# Sheet1.net
KiCad netlist of a schematic drawn in Altium Designer
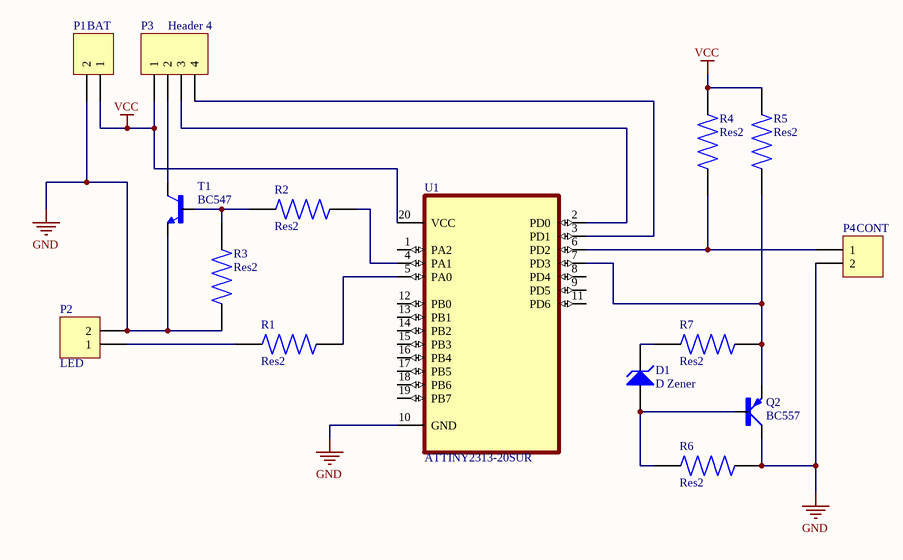
[diagram p0: Sheet1.SchDoc]

(export (version "E")
  (design (tool "Eeschema 10.0.6"))
  (components
    (comp (ref "D1")
      (value "D Zener")
      (footprint "DIODE-0.7")
      (description "Zener Diode")
      (fields (field (name "PUBLISHER") "Altium Limited"))
      (libsource (lib "Miscellaneous Devices") (part "D Zener"))
    )
    (comp (ref "P1")
      (value "BAT")
      (footprint "HDR1X2")
      (description "Header, 2-Pin")
      (fields (field (name "PUBLISHER") "Altium Limited"))
      (libsource (lib "Miscellaneous Connectors") (part "Header 2"))
    )
    (comp (ref "P2")
      (value "LED")
      (footprint "HDR1X2")
      (description "Header, 2-Pin")
      (fields (field (name "PUBLISHER") "Altium Limited"))
      (libsource (lib "") (part "Header 2_1"))
    )
    (comp (ref "P3")
      (value "Header 4")
      (footprint "HDR1X4")
      (description "Header, 4-Pin")
      (fields (field (name "PUBLISHER") "Altium Limited"))
      (libsource (lib "Miscellaneous Connectors") (part "Header 4"))
    )
    (comp (ref "P4")
      (value "CONT")
      (footprint "HDR1X2")
      (description "Header, 2-Pin")
      (fields (field (name "PUBLISHER") "Altium Limited"))
      (libsource (lib "Miscellaneous Connectors") (part "Header 2"))
    )
    (comp (ref "Q2")
      (value "BC557")
      (footprint "SOT54A")
      (description "Bipolar (BJT) Transistor PNP 45 V 100 mA 320MHz 625 mW Through Hole TO-92 (TO-226)")
      (fields (field (name "MF") "ON Semiconductor"))
      (libsource (lib "BC557") (part "BC557"))
    )
    (comp (ref "R1")
      (value "Res2")
      (footprint "AXIAL-0.4")
      (description "Fixed Resistor CRGCQ 1206 10K 5%")
      (fields (field (name "MF") "TE Connectivity") (field (name "MP") "CRGCQ1206J10K"))
      (libsource (lib "CRGCQ1206J10K") (part "CRGCQ1206J10K"))
    )
    (comp (ref "R2")
      (value "Res2")
      (footprint "AXIAL-0.4")
      (description "Fixed Resistor CRGCQ 1206 10K 5%")
      (fields (field (name "MF") "TE Connectivity") (field (name "MP") "CRGCQ1206J10K"))
      (libsource (lib "CRGCQ1206J10K") (part "CRGCQ1206J10K"))
    )
    (comp (ref "R3")
      (value "Res2")
      (footprint "AXIAL-0.4")
      (description "Fixed Resistor CRGCQ 1206 10K 5%")
      (fields (field (name "MF") "TE Connectivity") (field (name "MP") "CRGCQ1206J10K"))
      (libsource (lib "CRGCQ1206J10K") (part "CRGCQ1206J10K"))
    )
    (comp (ref "R4")
      (value "Res2")
      (footprint "AXIAL-0.4")
      (description "Fixed Resistor CRGCQ 1206 10K 5%")
      (fields (field (name "MF") "TE Connectivity") (field (name "MP") "CRGCQ1206J10K"))
      (libsource (lib "CRGCQ1206J10K") (part "CRGCQ1206J10K"))
    )
    (comp (ref "R5")
      (value "Res2")
      (footprint "AXIAL-0.4")
      (description "Fixed Resistor CRGCQ 1206 10K 5%")
      (fields (field (name "MF") "TE Connectivity") (field (name "MP") "CRGCQ1206J10K"))
      (libsource (lib "CRGCQ1206J10K") (part "CRGCQ1206J10K"))
    )
    (comp (ref "R6")
      (value "Res2")
      (footprint "AXIAL-0.4")
      (description "Fixed Resistor CRGCQ 1206 10K 5%")
      (fields (field (name "MF") "TE Connectivity") (field (name "MP") "CRGCQ1206J10K"))
      (libsource (lib "") (part "CRGCQ1206J10K_2"))
    )
    (comp (ref "R7")
      (value "Res2")
      (footprint "AXIAL-0.4")
      (description "Fixed Resistor CRGCQ 1206 10K 5%")
      (fields (field (name "MF") "TE Connectivity") (field (name "MP") "CRGCQ1206J10K"))
      (libsource (lib "") (part "CRGCQ1206J10K_1"))
    )
    (comp (ref "T1")
      (value "BC547")
      (footprint "TO92")
      (description "Trans GP BJT NPN 45V 0.1A 500mW 3-Pin TO-92 T/R")
      (fields (field (name "MF") "ON Semiconductor"))
      (libsource (lib "BC547") (part "BC547"))
    )
    (comp (ref "U1")
      (value "ATTINY2313-20SUR")
      (footprint "SOIC127P1032X265-20N")
      (description "AVR series Microcontroller IC 8-Bit 20MHz 2KB (1K x 16) FLASH 20-SOIC")
      (fields (field (name "MF") "Microchip Technology"))
      (libsource (lib "ATTINY2313-20SUR") (part "ATTINY2313-20SUR"))
    )
  )
  (nets
    (net (code "1") (name "GND") (class "Default")
      (node (ref "P1") (pin "2") (pinfunction "2_2") (pintype "passive"))
      (node (ref "P2") (pin "2") (pinfunction "2_2") (pintype "passive"))
      (node (ref "P4") (pin "2") (pinfunction "2_2") (pintype "passive"))
      (node (ref "Q2") (pin "C") (pinfunction "C_C") (pintype "passive"))
      (node (ref "R3") (pin "1") (pinfunction "1_1") (pintype "passive"))
      (node (ref "R6") (pin "1") (pinfunction "1_1") (pintype "passive"))
      (node (ref "T1") (pin "1") (pinfunction "E_1") (pintype "passive"))
      (node (ref "U1") (pin "10") (pinfunction "GND_10") (pintype "passive"))
    )
    (net (code "2") (name "Net-(D1-A)") (class "Default")
      (node (ref "D1") (pin "1") (pinfunction "A_1") (pintype "passive"))
      (node (ref "Q2") (pin "B") (pinfunction "B_B") (pintype "passive"))
      (node (ref "R6") (pin "2") (pinfunction "2_2") (pintype "passive"))
    )
    (net (code "3") (name "Net-(D1-K)") (class "Default")
      (node (ref "D1") (pin "2") (pinfunction "K_2") (pintype "passive"))
      (node (ref "R7") (pin "1") (pinfunction "1_1") (pintype "passive"))
    )
    (net (code "4") (name "Net-(P2-Pad1)") (class "Default")
      (node (ref "P2") (pin "1") (pinfunction "1_1") (pintype "passive"))
      (node (ref "R1") (pin "1") (pinfunction "1_1") (pintype "passive"))
    )
    (net (code "5") (name "Net-(T1-B)") (class "Default")
      (node (ref "R2") (pin "1") (pinfunction "1_1") (pintype "passive"))
      (node (ref "R3") (pin "2") (pinfunction "2_2") (pintype "passive"))
      (node (ref "T1") (pin "2") (pinfunction "B_2") (pintype "passive"))
    )
    (net (code "6") (name "Net-(T1-C)") (class "Default")
      (node (ref "P3") (pin "2") (pinfunction "2_2") (pintype "passive"))
      (node (ref "T1") (pin "3") (pinfunction "C_3") (pintype "passive"))
    )
    (net (code "7") (name "Net-(U1-PA0)") (class "Default")
      (node (ref "R1") (pin "2") (pinfunction "2_2") (pintype "passive"))
      (node (ref "U1") (pin "5") (pinfunction "PA0_5") (pintype "bidirectional"))
    )
    (net (code "8") (name "Net-(U1-PA1)") (class "Default")
      (node (ref "R2") (pin "2") (pinfunction "2_2") (pintype "passive"))
      (node (ref "U1") (pin "4") (pinfunction "PA1_4") (pintype "bidirectional"))
    )
    (net (code "9") (name "Net-(U1-PD0)") (class "Default")
      (node (ref "P3") (pin "3") (pinfunction "3_3") (pintype "passive"))
      (node (ref "U1") (pin "2") (pinfunction "PD0_2") (pintype "bidirectional"))
    )
    (net (code "10") (name "Net-(U1-PD1)") (class "Default")
      (node (ref "P3") (pin "4") (pinfunction "4_4") (pintype "passive"))
      (node (ref "U1") (pin "3") (pinfunction "PD1_3") (pintype "bidirectional"))
    )
    (net (code "11") (name "Net-(U1-PD2)") (class "Default")
      (node (ref "P4") (pin "1") (pinfunction "1_1") (pintype "passive"))
      (node (ref "R4") (pin "1") (pinfunction "1_1") (pintype "passive"))
      (node (ref "U1") (pin "6") (pinfunction "PD2_6") (pintype "bidirectional"))
    )
    (net (code "12") (name "Net-(U1-PD3)") (class "Default")
      (node (ref "Q2") (pin "E") (pinfunction "E_E") (pintype "passive"))
      (node (ref "R5") (pin "1") (pinfunction "1_1") (pintype "passive"))
      (node (ref "R7") (pin "1") (pinfunction "1_1") (pintype "passive"))
      (node (ref "U1") (pin "7") (pinfunction "PD3_7") (pintype "bidirectional"))
    )
    (net (code "13") (name "VCC") (class "Default")
      (node (ref "P1") (pin "1") (pinfunction "1_1") (pintype "passive"))
      (node (ref "P3") (pin "1") (pinfunction "1_1") (pintype "passive"))
      (node (ref "R4") (pin "2") (pinfunction "2_2") (pintype "passive"))
      (node (ref "R5") (pin "2") (pinfunction "2_2") (pintype "passive"))
      (node (ref "U1") (pin "20") (pinfunction "VCC_20") (pintype "power_in"))
    )
    (net (code "14") (name "unconnected-(U1-PA2-Pad1)") (class "Default")
      (node (ref "U1") (pin "1") (pinfunction "PA2_1") (pintype "bidirectional"))
    )
    (net (code "15") (name "unconnected-(U1-PB0-Pad12)") (class "Default")
      (node (ref "U1") (pin "12") (pinfunction "PB0_12") (pintype "bidirectional"))
    )
    (net (code "16") (name "unconnected-(U1-PB1-Pad13)") (class "Default")
      (node (ref "U1") (pin "13") (pinfunction "PB1_13") (pintype "bidirectional"))
    )
    (net (code "17") (name "unconnected-(U1-PB2-Pad14)") (class "Default")
      (node (ref "U1") (pin "14") (pinfunction "PB2_14") (pintype "bidirectional"))
    )
    (net (code "18") (name "unconnected-(U1-PB3-Pad15)") (class "Default")
      (node (ref "U1") (pin "15") (pinfunction "PB3_15") (pintype "bidirectional"))
    )
    (net (code "19") (name "unconnected-(U1-PB4-Pad16)") (class "Default")
      (node (ref "U1") (pin "16") (pinfunction "PB4_16") (pintype "bidirectional"))
    )
    (net (code "20") (name "unconnected-(U1-PB5-Pad17)") (class "Default")
      (node (ref "U1") (pin "17") (pinfunction "PB5_17") (pintype "bidirectional"))
    )
    (net (code "21") (name "unconnected-(U1-PB6-Pad18)") (class "Default")
      (node (ref "U1") (pin "18") (pinfunction "PB6_18") (pintype "bidirectional"))
    )
    (net (code "22") (name "unconnected-(U1-PB7-Pad19)") (class "Default")
      (node (ref "U1") (pin "19") (pinfunction "PB7_19") (pintype "bidirectional"))
    )
    (net (code "23") (name "unconnected-(U1-PD4-Pad8)") (class "Default")
      (node (ref "U1") (pin "8") (pinfunction "PD4_8") (pintype "bidirectional"))
    )
    (net (code "24") (name "unconnected-(U1-PD5-Pad9)") (class "Default")
      (node (ref "U1") (pin "9") (pinfunction "PD5_9") (pintype "bidirectional"))
    )
    (net (code "25") (name "unconnected-(U1-PD6-Pad11)") (class "Default")
      (node (ref "U1") (pin "11") (pinfunction "PD6_11") (pintype "bidirectional"))
    )
  )
)
